# CON_PCI_Express_X8_98PIN.net
KiCad netlist of a schematic drawn in Altium Designer
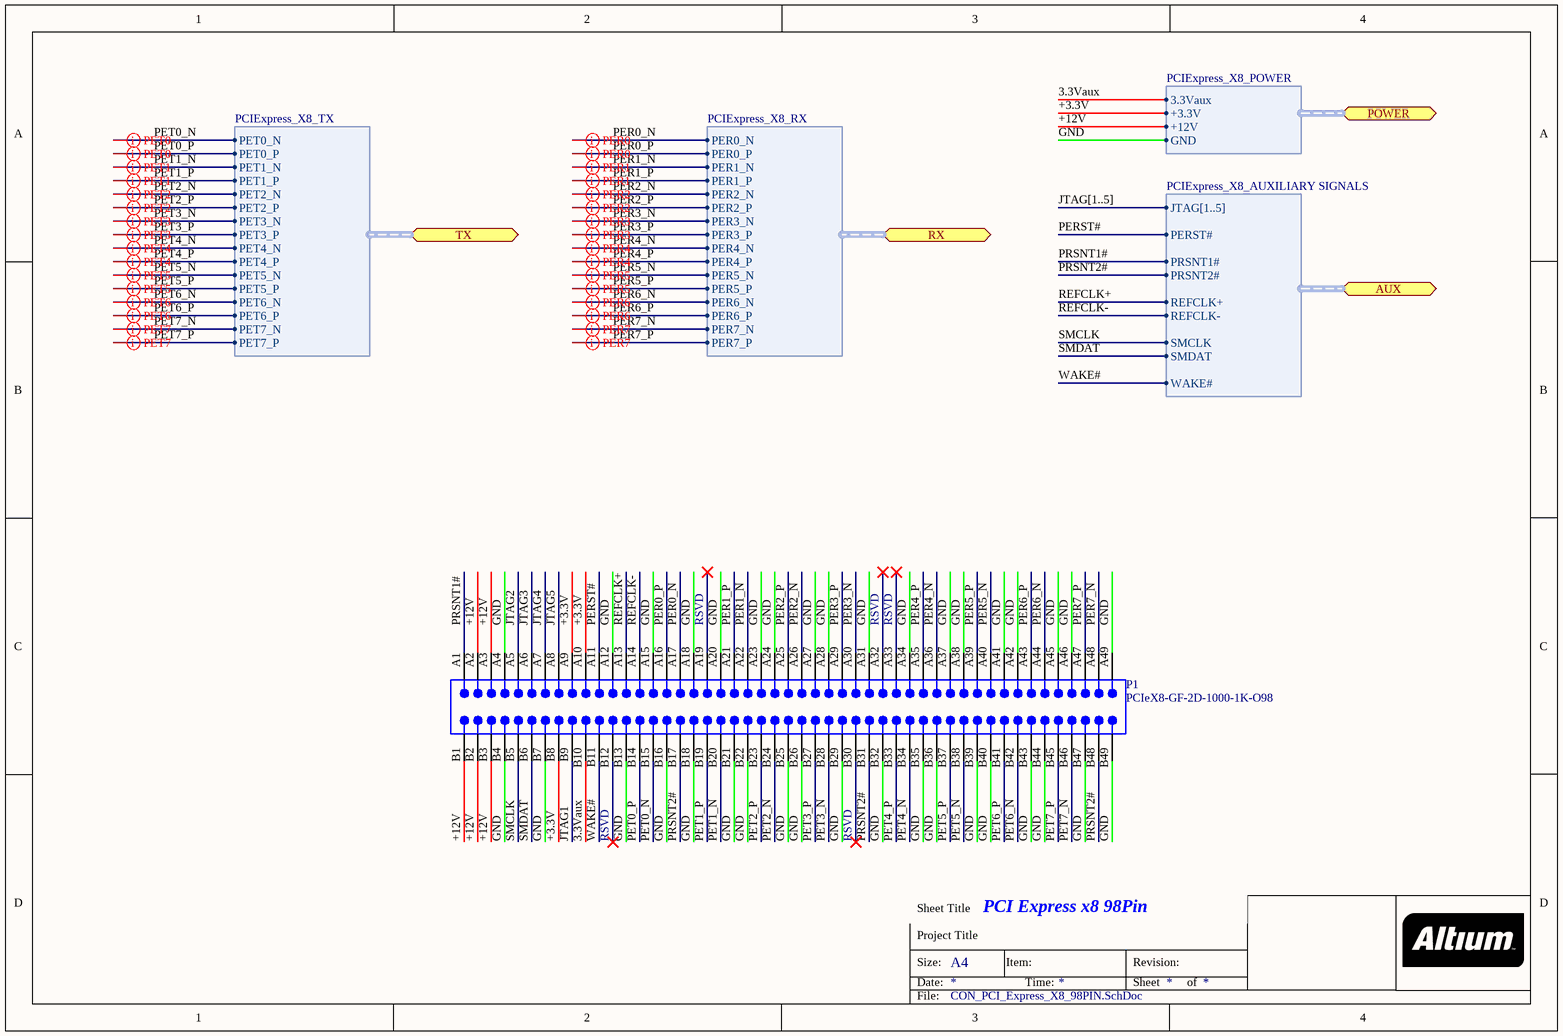
[diagram p0: CON_PCI_Express_X8_98PIN.SchDoc]

(export (version "E")
  (design (tool "Eeschema 10.0.6"))
  (components
    (comp (ref "P1")
      (value "PCIeX8-GF-2D-1000-1K-O98")
      (footprint "PCIeX8-GF-2D-1000-1K-O98")
      (description "Golden finger, PCIeX8, Dual, Opposite, Pitch 1mm, 98-Position")
      (fields (field (name "PUBLISHER") "Altium"))
      (libsource (lib "Altium Shanghai") (part "PCIeX8-GF-2D-1000-1K-O98"))
    )
  )
  (nets
    (net (code "7") (name "/+3.3V") (class "Default")
      (node (ref "P1") (pin "A10") (pinfunction "A10_A10") (pintype "passive"))
      (node (ref "P1") (pin "A9") (pinfunction "A9_A9") (pintype "passive"))
      (node (ref "P1") (pin "B8") (pinfunction "B8_B8") (pintype "passive"))
    )
    (net (code "8") (name "/+12V") (class "Default")
      (node (ref "P1") (pin "A2") (pinfunction "A2_A2") (pintype "passive"))
      (node (ref "P1") (pin "A3") (pinfunction "A3_A3") (pintype "passive"))
      (node (ref "P1") (pin "B1") (pinfunction "B1_B1") (pintype "passive"))
      (node (ref "P1") (pin "B2") (pinfunction "B2_B2") (pintype "passive"))
      (node (ref "P1") (pin "B3") (pinfunction "B3_B3") (pintype "passive"))
    )
    (net (code "9") (name "/3.3Vaux") (class "Default")
      (node (ref "P1") (pin "B10") (pinfunction "B10_B10") (pintype "passive"))
    )
    (net (code "11") (name "/GND") (class "Default")
      (node (ref "P1") (pin "A12") (pinfunction "A12_A12") (pintype "passive"))
      (node (ref "P1") (pin "A15") (pinfunction "A15_A15") (pintype "passive"))
      (node (ref "P1") (pin "A18") (pinfunction "A18_A18") (pintype "passive"))
      (node (ref "P1") (pin "A20") (pinfunction "A20_A20") (pintype "passive"))
      (node (ref "P1") (pin "A23") (pinfunction "A23_A23") (pintype "passive"))
      (node (ref "P1") (pin "A24") (pinfunction "A24_A24") (pintype "passive"))
      (node (ref "P1") (pin "A27") (pinfunction "A27_A27") (pintype "passive"))
      (node (ref "P1") (pin "A28") (pinfunction "A28_A28") (pintype "passive"))
      (node (ref "P1") (pin "A31") (pinfunction "A31_A31") (pintype "passive"))
      (node (ref "P1") (pin "A34") (pinfunction "A34_A34") (pintype "passive"))
      (node (ref "P1") (pin "A37") (pinfunction "A37_A37") (pintype "passive"))
      (node (ref "P1") (pin "A38") (pinfunction "A38_A38") (pintype "passive"))
      (node (ref "P1") (pin "A4") (pinfunction "A4_A4") (pintype "passive"))
      (node (ref "P1") (pin "A41") (pinfunction "A41_A41") (pintype "passive"))
      (node (ref "P1") (pin "A42") (pinfunction "A42_A42") (pintype "passive"))
      (node (ref "P1") (pin "A45") (pinfunction "A45_A45") (pintype "passive"))
      (node (ref "P1") (pin "A46") (pinfunction "A46_A46") (pintype "passive"))
      (node (ref "P1") (pin "A49") (pinfunction "A49_A49") (pintype "passive"))
      (node (ref "P1") (pin "B13") (pinfunction "B13_B13") (pintype "passive"))
      (node (ref "P1") (pin "B16") (pinfunction "B16_B16") (pintype "passive"))
      (node (ref "P1") (pin "B18") (pinfunction "B18_B18") (pintype "passive"))
      (node (ref "P1") (pin "B21") (pinfunction "B21_B21") (pintype "passive"))
      (node (ref "P1") (pin "B22") (pinfunction "B22_B22") (pintype "passive"))
      (node (ref "P1") (pin "B25") (pinfunction "B25_B25") (pintype "passive"))
      (node (ref "P1") (pin "B26") (pinfunction "B26_B26") (pintype "passive"))
      (node (ref "P1") (pin "B29") (pinfunction "B29_B29") (pintype "passive"))
      (node (ref "P1") (pin "B32") (pinfunction "B32_B32") (pintype "passive"))
      (node (ref "P1") (pin "B35") (pinfunction "B35_B35") (pintype "passive"))
      (node (ref "P1") (pin "B36") (pinfunction "B36_B36") (pintype "passive"))
      (node (ref "P1") (pin "B39") (pinfunction "B39_B39") (pintype "passive"))
      (node (ref "P1") (pin "B4") (pinfunction "B4_B4") (pintype "passive"))
      (node (ref "P1") (pin "B40") (pinfunction "B40_B40") (pintype "passive"))
      (node (ref "P1") (pin "B43") (pinfunction "B43_B43") (pintype "passive"))
      (node (ref "P1") (pin "B44") (pinfunction "B44_B44") (pintype "passive"))
      (node (ref "P1") (pin "B47") (pinfunction "B47_B47") (pintype "passive"))
      (node (ref "P1") (pin "B49") (pinfunction "B49_B49") (pintype "passive"))
      (node (ref "P1") (pin "B7") (pinfunction "B7_B7") (pintype "passive"))
    )
    (net (code "12") (name "/JTAG1") (class "Default")
      (node (ref "P1") (pin "B9") (pinfunction "B9_B9") (pintype "passive"))
    )
    (net (code "13") (name "/JTAG2") (class "Default")
      (node (ref "P1") (pin "A5") (pinfunction "A5_A5") (pintype "passive"))
    )
    (net (code "14") (name "/JTAG3") (class "Default")
      (node (ref "P1") (pin "A6") (pinfunction "A6_A6") (pintype "passive"))
    )
    (net (code "15") (name "/JTAG4") (class "Default")
      (node (ref "P1") (pin "A7") (pinfunction "A7_A7") (pintype "passive"))
    )
    (net (code "16") (name "/JTAG5") (class "Default")
      (node (ref "P1") (pin "A8") (pinfunction "A8_A8") (pintype "passive"))
    )
    (net (code "17") (name "/PER0_N") (class "Default")
      (node (ref "P1") (pin "A17") (pinfunction "A17_A17") (pintype "passive"))
    )
    (net (code "18") (name "/PER0_P") (class "Default")
      (node (ref "P1") (pin "A16") (pinfunction "A16_A16") (pintype "passive"))
    )
    (net (code "19") (name "/PER1_N") (class "Default")
      (node (ref "P1") (pin "A22") (pinfunction "A22_A22") (pintype "passive"))
    )
    (net (code "20") (name "/PER1_P") (class "Default")
      (node (ref "P1") (pin "A21") (pinfunction "A21_A21") (pintype "passive"))
    )
    (net (code "21") (name "/PER2_N") (class "Default")
      (node (ref "P1") (pin "A26") (pinfunction "A26_A26") (pintype "passive"))
    )
    (net (code "22") (name "/PER2_P") (class "Default")
      (node (ref "P1") (pin "A25") (pinfunction "A25_A25") (pintype "passive"))
    )
    (net (code "23") (name "/PER3_N") (class "Default")
      (node (ref "P1") (pin "A30") (pinfunction "A30_A30") (pintype "passive"))
    )
    (net (code "24") (name "/PER3_P") (class "Default")
      (node (ref "P1") (pin "A29") (pinfunction "A29_A29") (pintype "passive"))
    )
    (net (code "25") (name "/PER4_N") (class "Default")
      (node (ref "P1") (pin "A36") (pinfunction "A36_A36") (pintype "passive"))
    )
    (net (code "26") (name "/PER4_P") (class "Default")
      (node (ref "P1") (pin "A35") (pinfunction "A35_A35") (pintype "passive"))
    )
    (net (code "27") (name "/PER5_N") (class "Default")
      (node (ref "P1") (pin "A40") (pinfunction "A40_A40") (pintype "passive"))
    )
    (net (code "28") (name "/PER5_P") (class "Default")
      (node (ref "P1") (pin "A39") (pinfunction "A39_A39") (pintype "passive"))
    )
    (net (code "29") (name "/PER6_N") (class "Default")
      (node (ref "P1") (pin "A44") (pinfunction "A44_A44") (pintype "passive"))
    )
    (net (code "30") (name "/PER6_P") (class "Default")
      (node (ref "P1") (pin "A43") (pinfunction "A43_A43") (pintype "passive"))
    )
    (net (code "31") (name "/PER7_N") (class "Default")
      (node (ref "P1") (pin "A48") (pinfunction "A48_A48") (pintype "passive"))
    )
    (net (code "32") (name "/PER7_P") (class "Default")
      (node (ref "P1") (pin "A47") (pinfunction "A47_A47") (pintype "passive"))
    )
    (net (code "33") (name "/PERST#") (class "Default")
      (node (ref "P1") (pin "A11") (pinfunction "A11_A11") (pintype "passive"))
    )
    (net (code "34") (name "/PET0_N") (class "Default")
      (node (ref "P1") (pin "B15") (pinfunction "B15_B15") (pintype "passive"))
    )
    (net (code "35") (name "/PET0_P") (class "Default")
      (node (ref "P1") (pin "B14") (pinfunction "B14_B14") (pintype "passive"))
    )
    (net (code "36") (name "/PET1_N") (class "Default")
      (node (ref "P1") (pin "B20") (pinfunction "B20_B20") (pintype "passive"))
    )
    (net (code "37") (name "/PET1_P") (class "Default")
      (node (ref "P1") (pin "B19") (pinfunction "B19_B19") (pintype "passive"))
    )
    (net (code "38") (name "/PET2_N") (class "Default")
      (node (ref "P1") (pin "B24") (pinfunction "B24_B24") (pintype "passive"))
    )
    (net (code "39") (name "/PET2_P") (class "Default")
      (node (ref "P1") (pin "B23") (pinfunction "B23_B23") (pintype "passive"))
    )
    (net (code "40") (name "/PET3_N") (class "Default")
      (node (ref "P1") (pin "B28") (pinfunction "B28_B28") (pintype "passive"))
    )
    (net (code "41") (name "/PET3_P") (class "Default")
      (node (ref "P1") (pin "B27") (pinfunction "B27_B27") (pintype "passive"))
    )
    (net (code "42") (name "/PET4_N") (class "Default")
      (node (ref "P1") (pin "B34") (pinfunction "B34_B34") (pintype "passive"))
    )
    (net (code "43") (name "/PET4_P") (class "Default")
      (node (ref "P1") (pin "B33") (pinfunction "B33_B33") (pintype "passive"))
    )
    (net (code "44") (name "/PET5_N") (class "Default")
      (node (ref "P1") (pin "B38") (pinfunction "B38_B38") (pintype "passive"))
    )
    (net (code "45") (name "/PET5_P") (class "Default")
      (node (ref "P1") (pin "B37") (pinfunction "B37_B37") (pintype "passive"))
    )
    (net (code "46") (name "/PET6_N") (class "Default")
      (node (ref "P1") (pin "B42") (pinfunction "B42_B42") (pintype "passive"))
    )
    (net (code "47") (name "/PET6_P") (class "Default")
      (node (ref "P1") (pin "B41") (pinfunction "B41_B41") (pintype "passive"))
    )
    (net (code "48") (name "/PET7_N") (class "Default")
      (node (ref "P1") (pin "B46") (pinfunction "B46_B46") (pintype "passive"))
    )
    (net (code "49") (name "/PET7_P") (class "Default")
      (node (ref "P1") (pin "B45") (pinfunction "B45_B45") (pintype "passive"))
    )
    (net (code "50") (name "/PRSNT1#") (class "Default")
      (node (ref "P1") (pin "A1") (pinfunction "A1_A1") (pintype "passive"))
    )
    (net (code "51") (name "/PRSNT2#") (class "Default")
      (node (ref "P1") (pin "B17") (pinfunction "B17_B17") (pintype "passive"))
      (node (ref "P1") (pin "B31") (pinfunction "B31_B31") (pintype "passive"))
      (node (ref "P1") (pin "B48") (pinfunction "B48_B48") (pintype "passive"))
    )
    (net (code "52") (name "/REFCLK+") (class "Default")
      (node (ref "P1") (pin "A13") (pinfunction "A13_A13") (pintype "passive"))
    )
    (net (code "53") (name "/REFCLK-") (class "Default")
      (node (ref "P1") (pin "A14") (pinfunction "A14_A14") (pintype "passive"))
    )
    (net (code "54") (name "/SMCLK") (class "Default")
      (node (ref "P1") (pin "B5") (pinfunction "B5_B5") (pintype "passive"))
    )
    (net (code "55") (name "/SMDAT") (class "Default")
      (node (ref "P1") (pin "B6") (pinfunction "B6_B6") (pintype "passive"))
    )
    (net (code "56") (name "/WAKE#") (class "Default")
      (node (ref "P1") (pin "B11") (pinfunction "B11_B11") (pintype "passive"))
    )
    (net (code "61") (name "unconnected-(P1-PadA19)") (class "Default")
      (node (ref "P1") (pin "A19") (pinfunction "A19_A19") (pintype "passive+no_connect"))
    )
    (net (code "62") (name "unconnected-(P1-PadA32)") (class "Default")
      (node (ref "P1") (pin "A32") (pinfunction "A32_A32") (pintype "passive+no_connect"))
    )
    (net (code "63") (name "unconnected-(P1-PadA33)") (class "Default")
      (node (ref "P1") (pin "A33") (pinfunction "A33_A33") (pintype "passive+no_connect"))
    )
    (net (code "64") (name "unconnected-(P1-PadB12)") (class "Default")
      (node (ref "P1") (pin "B12") (pinfunction "B12_B12") (pintype "passive+no_connect"))
    )
    (net (code "65") (name "unconnected-(P1-PadB30)") (class "Default")
      (node (ref "P1") (pin "B30") (pinfunction "B30_B30") (pintype "passive+no_connect"))
    )
  )
)
